# rapidshark-display-shifter-mk-2_2.net
KiCad netlist of a schematic drawn in EAGLE
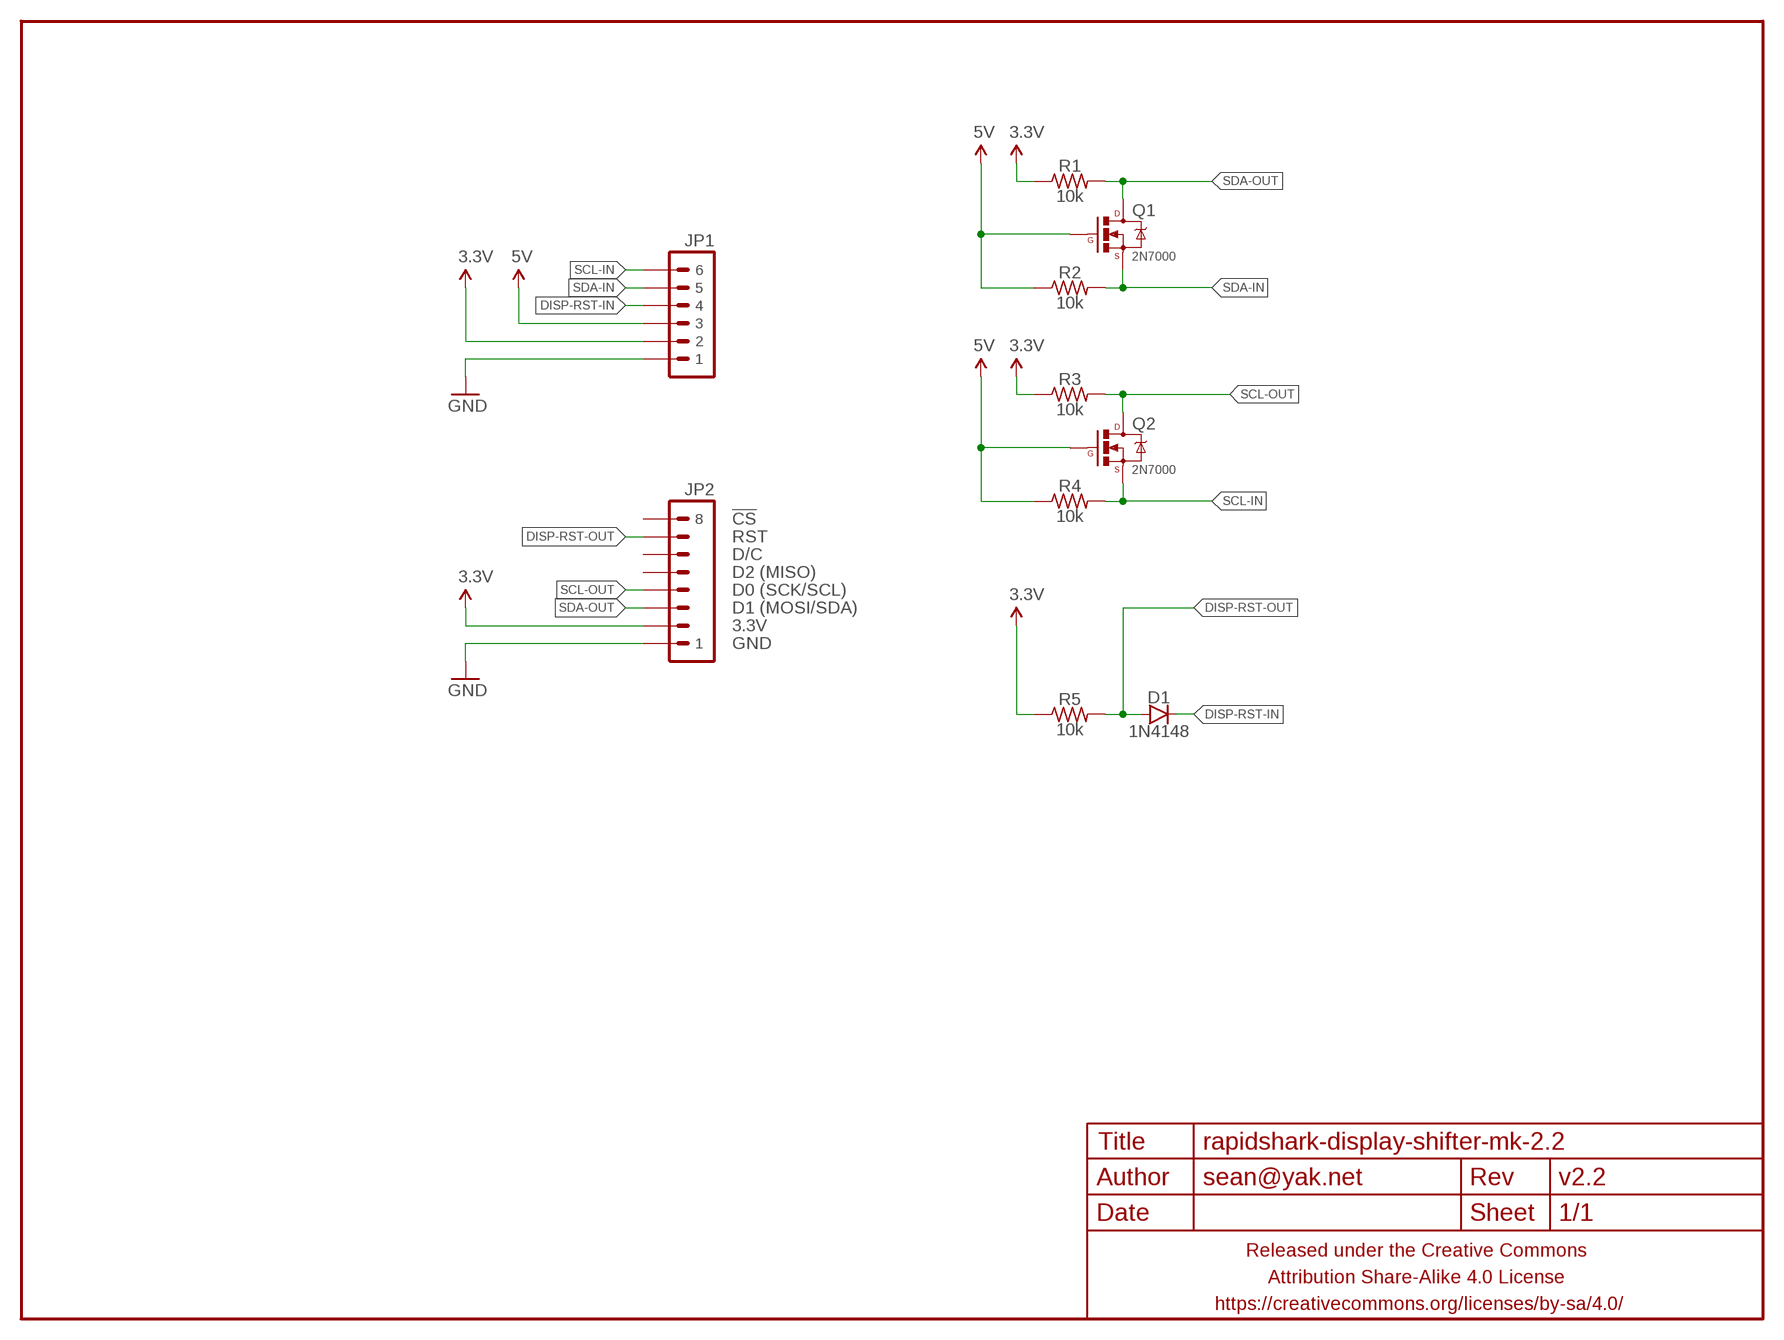
[diagram p0: schematic, sheet 1]

(export (version "E")
  (design (tool "Eeschema 10.0.6"))
  (components
    (comp (ref "D1")
      (value "1N4148")
      (footprint "eagle-import:DIODE-7.62MM")
      (libsource (lib "eagle-import") (part "DIODEPTH-7.62MM"))
    )
    (comp (ref "FRAME1")
      (value "FRAME-LETTERNO_PACKAGE")
      (footprint "eagle-import:DUMMY")
      (fields (field (name "DESIGNER") "sean@yak.net") (field (name "VERSION") "v2.2"))
      (libsource (lib "eagle-import") (part "FRAME-LETTERNO_PACKAGE"))
    )
    (comp (ref "JP1")
      (value "M06JST-PH-PTH-VERT")
      (footprint "eagle-import:JST-6-PH-VERT-PTH")
      (libsource (lib "eagle-import") (part "M06JST-PH-PTH-VERT"))
    )
    (comp (ref "JP2")
      (value "M08PTH-1.2MMHOLES")
      (footprint "eagle-import:1X08-1.2MMHOLES")
      (libsource (lib "eagle-import") (part "M08PTH-1.2MMHOLES"))
    )
    (comp (ref "Q1")
      (value "2N7000")
      (footprint "eagle-import:TO-92-AMMO")
      (libsource (lib "eagle-import") (part "MOSFET-NCHANNEL2N7000-AMMO"))
    )
    (comp (ref "Q2")
      (value "2N7000")
      (footprint "eagle-import:TO-92-AMMO")
      (libsource (lib "eagle-import") (part "MOSFET-NCHANNEL2N7000-AMMO"))
    )
    (comp (ref "R1")
      (value "10k")
      (footprint "eagle-import:RESISTOR-AXIAL-PTH-5.08MM")
      (libsource (lib "eagle-import") (part "RESISTORPTH-AXIAL-5.08MM"))
    )
    (comp (ref "R2")
      (value "10k")
      (footprint "eagle-import:RESISTOR-AXIAL-PTH-5.08MM")
      (libsource (lib "eagle-import") (part "RESISTORPTH-AXIAL-5.08MM"))
    )
    (comp (ref "R3")
      (value "10k")
      (footprint "eagle-import:RESISTOR-AXIAL-PTH-5.08MM")
      (libsource (lib "eagle-import") (part "RESISTORPTH-AXIAL-5.08MM"))
    )
    (comp (ref "R4")
      (value "10k")
      (footprint "eagle-import:RESISTOR-AXIAL-PTH-5.08MM")
      (libsource (lib "eagle-import") (part "RESISTORPTH-AXIAL-5.08MM"))
    )
    (comp (ref "R5")
      (value "10k")
      (footprint "eagle-import:RESISTOR-AXIAL-PTH-5.08MM")
      (libsource (lib "eagle-import") (part "RESISTORPTH-AXIAL-5.08MM"))
    )
  )
  (nets
    (net (code "1") (name "3.3V") (class "Default")
      (node (ref "JP1") (pin "2") (pinfunction "2_2") (pintype "passive"))
      (node (ref "JP2") (pin "2") (pinfunction "2_2") (pintype "passive"))
      (node (ref "R1") (pin "P$1") (pinfunction "1_P$1") (pintype "passive"))
      (node (ref "R3") (pin "P$1") (pinfunction "1_P$1") (pintype "passive"))
      (node (ref "R5") (pin "P$1") (pinfunction "1_P$1") (pintype "passive"))
    )
    (net (code "2") (name "5V") (class "Default")
      (node (ref "JP1") (pin "3") (pinfunction "3_3") (pintype "passive"))
      (node (ref "Q1") (pin "2") (pinfunction "G_2") (pintype "passive"))
      (node (ref "Q2") (pin "2") (pinfunction "G_2") (pintype "passive"))
      (node (ref "R2") (pin "P$1") (pinfunction "1_P$1") (pintype "passive"))
      (node (ref "R4") (pin "P$1") (pinfunction "1_P$1") (pintype "passive"))
    )
    (net (code "3") (name "DISP-RST-IN") (class "Default")
      (node (ref "D1") (pin "K") (pinfunction "C_K") (pintype "passive"))
      (node (ref "JP1") (pin "4") (pinfunction "4_4") (pintype "passive"))
    )
    (net (code "4") (name "DISP-RST-OUT") (class "Default")
      (node (ref "D1") (pin "A") (pinfunction "A_A") (pintype "passive"))
      (node (ref "JP2") (pin "7") (pinfunction "7_7") (pintype "passive"))
      (node (ref "R5") (pin "P$2") (pinfunction "2_P$2") (pintype "passive"))
    )
    (net (code "5") (name "GND") (class "Default")
      (node (ref "JP1") (pin "1") (pinfunction "1_1") (pintype "passive"))
      (node (ref "JP2") (pin "1") (pinfunction "1_1") (pintype "passive"))
    )
    (net (code "6") (name "SCL-IN") (class "Default")
      (node (ref "JP1") (pin "6") (pinfunction "6_6") (pintype "passive"))
      (node (ref "Q2") (pin "1") (pinfunction "S_1") (pintype "passive"))
      (node (ref "R4") (pin "P$2") (pinfunction "2_P$2") (pintype "passive"))
    )
    (net (code "7") (name "SCL-OUT") (class "Default")
      (node (ref "JP2") (pin "4") (pinfunction "4_4") (pintype "passive"))
      (node (ref "Q2") (pin "3") (pinfunction "D_3") (pintype "passive"))
      (node (ref "R3") (pin "P$2") (pinfunction "2_P$2") (pintype "passive"))
    )
    (net (code "8") (name "SDA-IN") (class "Default")
      (node (ref "JP1") (pin "5") (pinfunction "5_5") (pintype "passive"))
      (node (ref "Q1") (pin "1") (pinfunction "S_1") (pintype "passive"))
      (node (ref "R2") (pin "P$2") (pinfunction "2_P$2") (pintype "passive"))
    )
    (net (code "9") (name "SDA-OUT") (class "Default")
      (node (ref "JP2") (pin "3") (pinfunction "3_3") (pintype "passive"))
      (node (ref "Q1") (pin "3") (pinfunction "D_3") (pintype "passive"))
      (node (ref "R1") (pin "P$2") (pinfunction "2_P$2") (pintype "passive"))
    )
    (net (code "10") (name "unconnected-(JP2-Pad5)") (class "Default")
      (node (ref "JP2") (pin "5") (pinfunction "5_5") (pintype "passive"))
    )
    (net (code "11") (name "unconnected-(JP2-Pad6)") (class "Default")
      (node (ref "JP2") (pin "6") (pinfunction "6_6") (pintype "passive"))
    )
    (net (code "12") (name "unconnected-(JP2-Pad8)") (class "Default")
      (node (ref "JP2") (pin "8") (pinfunction "8_8") (pintype "passive"))
    )
  )
)
